# myCar.net
KiCad netlist of a schematic drawn in Altium Designer
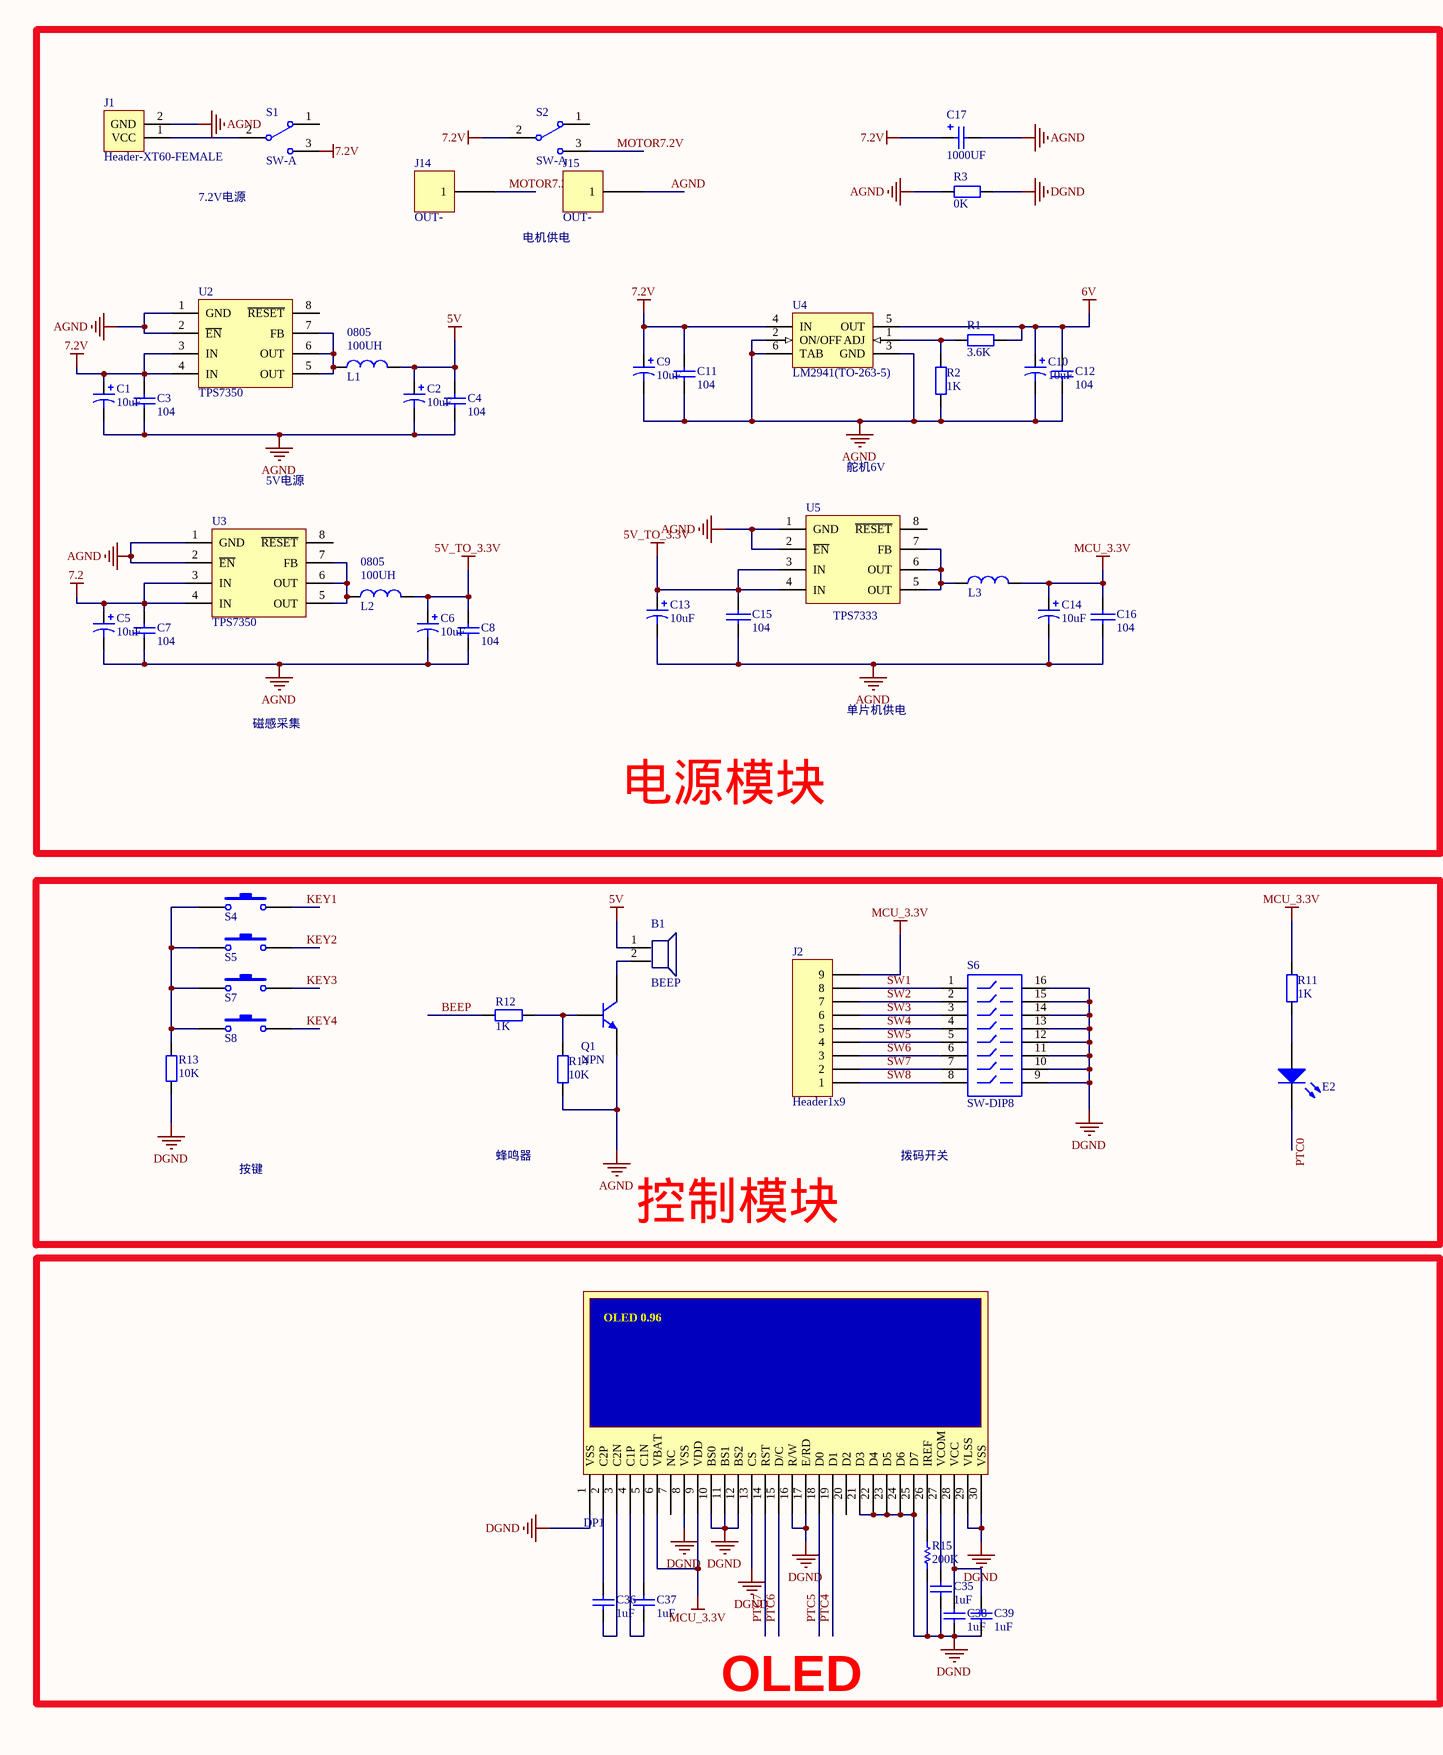
[diagram p0: myCar.SchDoc, left]
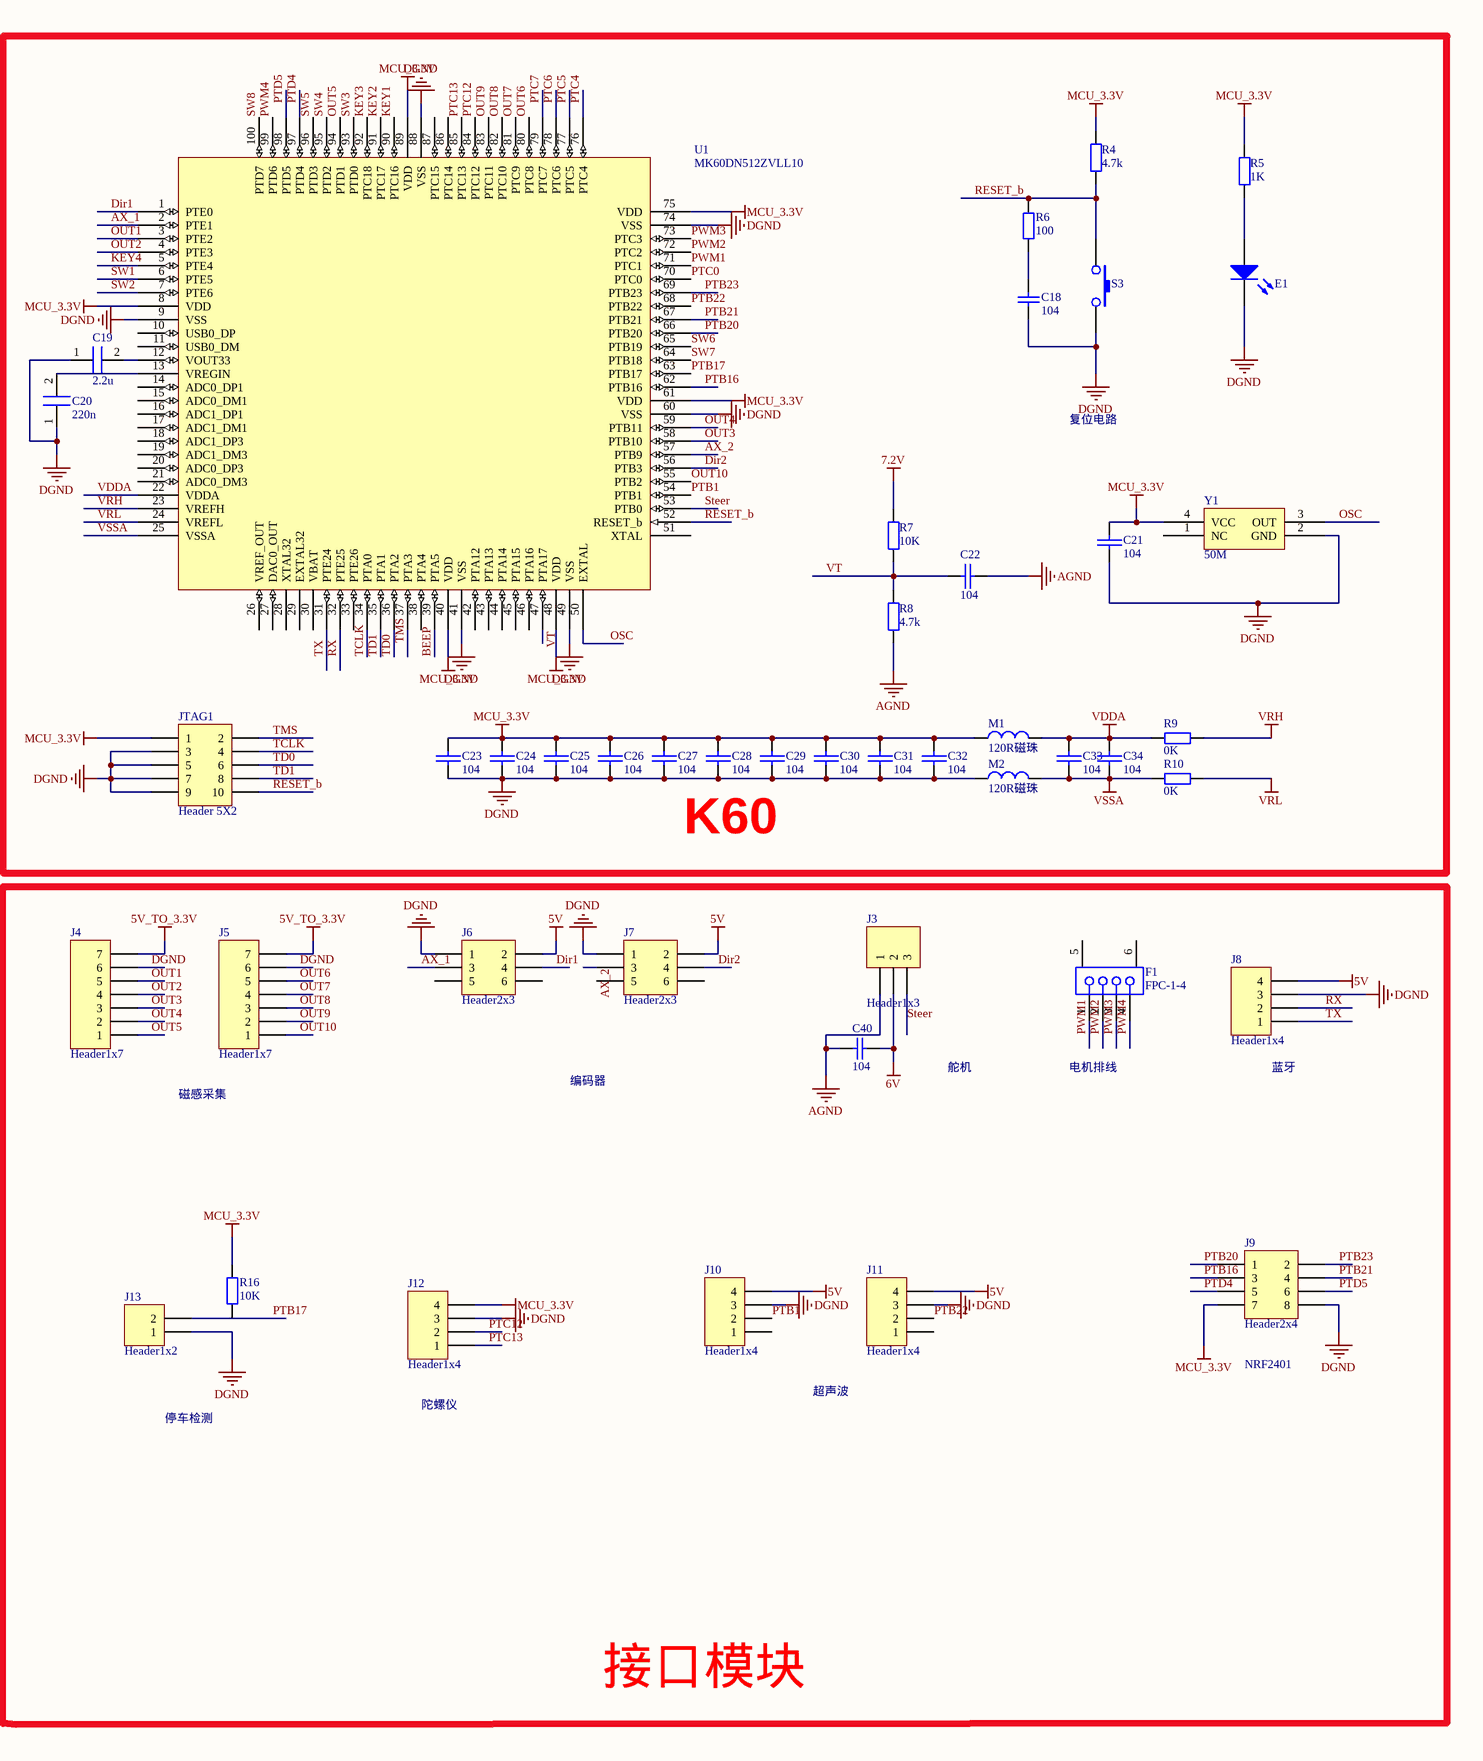
[diagram p1: myCar.SchDoc, right]

(export (version "E")
  (design (tool "Eeschema 10.0.6"))
  (components
    (comp (ref "B1") (value "BEEP") (footprint "BEEP0905") (libsource (lib "进击的袋鼠主板") (part "BEEP0905")))
    (comp (ref "C1")
      (value "10uF")
      (footprint "CAP_3216（1206）")
      (description "Polarized Capacitor (Radial)")
      (fields (field (name "Comment") "10uF/16V") (field (name "PUBLISHER") "Altium Limited"))
      (libsource (lib "进击的袋鼠主板") (part "Cap Pol1"))
    )
    (comp (ref "C2")
      (value "10uF")
      (footprint "CAP_3216（1206）")
      (description "Polarized Capacitor (Radial)")
      (fields (field (name "Comment") "10uF/16V") (field (name "PUBLISHER") "Altium Limited"))
      (libsource (lib "进击的袋鼠主板") (part "Cap Pol1"))
    )
    (comp (ref "C3")
      (value "104")
      (footprint "0603RC")
      (description "Capacitor")
      (fields (field (name "PUBLISHER") "Altium Limited"))
      (libsource (lib "进击的袋鼠主板") (part "Cap"))
    )
    (comp (ref "C4")
      (value "104")
      (footprint "0603RC")
      (description "Capacitor")
      (fields (field (name "PUBLISHER") "Altium Limited"))
      (libsource (lib "进击的袋鼠主板") (part "Cap"))
    )
    (comp (ref "C5")
      (value "10uF")
      (footprint "CAP_3216（1206）")
      (description "Polarized Capacitor (Radial)")
      (fields (field (name "Comment") "10uF/16V") (field (name "PUBLISHER") "Altium Limited"))
      (libsource (lib "进击的袋鼠主板") (part "Cap Pol1"))
    )
    (comp (ref "C6")
      (value "10uF")
      (footprint "CAP_3216（1206）")
      (description "Polarized Capacitor (Radial)")
      (fields (field (name "Comment") "10uF/16V") (field (name "PUBLISHER") "Altium Limited"))
      (libsource (lib "进击的袋鼠主板") (part "Cap Pol1"))
    )
    (comp (ref "C7")
      (value "104")
      (footprint "0603RC")
      (description "Capacitor")
      (fields (field (name "PUBLISHER") "Altium Limited"))
      (libsource (lib "进击的袋鼠主板") (part "Cap"))
    )
    (comp (ref "C8")
      (value "104")
      (footprint "0603RC")
      (description "Capacitor")
      (fields (field (name "PUBLISHER") "Altium Limited"))
      (libsource (lib "进击的袋鼠主板") (part "Cap"))
    )
    (comp (ref "C9")
      (value "10uF")
      (footprint "CAP_3216（1206）")
      (description "Polarized Capacitor (Radial)")
      (fields (field (name "Comment") "10uF/16V") (field (name "PUBLISHER") "Altium Limited"))
      (libsource (lib "进击的袋鼠主板") (part "Cap Pol1"))
    )
    (comp (ref "C10")
      (value "10uF")
      (footprint "CAP_3216（1206）")
      (description "Polarized Capacitor (Radial)")
      (fields (field (name "Comment") "10uF/16V") (field (name "PUBLISHER") "Altium Limited"))
      (libsource (lib "进击的袋鼠主板") (part "Cap Pol1"))
    )
    (comp (ref "C11")
      (value "104")
      (footprint "0603RC")
      (description "Capacitor")
      (fields (field (name "PUBLISHER") "Altium Limited"))
      (libsource (lib "进击的袋鼠主板") (part "Cap"))
    )
    (comp (ref "C12")
      (value "104")
      (footprint "0603RC")
      (description "Capacitor")
      (fields (field (name "PUBLISHER") "Altium Limited"))
      (libsource (lib "进击的袋鼠主板") (part "Cap"))
    )
    (comp (ref "C13")
      (value "10uF")
      (footprint "CAP_3216（1206）")
      (description "Polarized Capacitor (Radial)")
      (fields (field (name "Comment") "10uF/16V") (field (name "PUBLISHER") "Altium Limited"))
      (libsource (lib "进击的袋鼠主板") (part "Cap Pol1"))
    )
    (comp (ref "C14")
      (value "10uF")
      (footprint "CAP_3216（1206）")
      (description "Polarized Capacitor (Radial)")
      (fields (field (name "Comment") "10uF/16V") (field (name "PUBLISHER") "Altium Limited"))
      (libsource (lib "进击的袋鼠主板") (part "Cap Pol1"))
    )
    (comp (ref "C15")
      (value "104")
      (footprint "0603RC")
      (description "Capacitor")
      (libsource (lib "进击的袋鼠主板") (part "CAP_1"))
    )
    (comp (ref "C16")
      (value "104")
      (footprint "0603RC")
      (description "Capacitor")
      (libsource (lib "进击的袋鼠主板") (part "CAP_1"))
    )
    (comp (ref "C17")
      (value "CAP-SMD-1000UF")
      (footprint "CAP-SMD-1000UF")
      (fields (field (name "ALTIUM_UNNAMED_1") "1000UF"))
      (libsource (lib "进击的袋鼠主板") (part "CAP-SMD-1000UF"))
    )
    (comp (ref "C18")
      (value "104")
      (footprint "0603RC")
      (description "Capacitor")
      (fields (field (name "PUBLISHER") "Altium Limited"))
      (libsource (lib "进击的袋鼠主板") (part "Cap"))
    )
    (comp (ref "C19")
      (value "C0603")
      (footprint "0603RC")
      (fields (field (name "C") "2.2u"))
      (libsource (lib "进击的袋鼠主板") (part "C0603"))
    )
    (comp (ref "C20")
      (value "C0603")
      (footprint "0603RC")
      (fields (field (name "C") "220n"))
      (libsource (lib "进击的袋鼠主板") (part "C0603"))
    )
    (comp (ref "C21")
      (value "104")
      (footprint "0603RC")
      (description "Capacitor")
      (libsource (lib "进击的袋鼠主板") (part "CAP_1"))
    )
    (comp (ref "C22")
      (value "104")
      (footprint "0603RC")
      (description "Capacitor")
      (libsource (lib "进击的袋鼠主板") (part "CAP_1"))
    )
    (comp (ref "C23")
      (value "104")
      (footprint "0603RC")
      (description "Capacitor")
      (libsource (lib "进击的袋鼠主板") (part "CAP_1"))
    )
    (comp (ref "C24")
      (value "104")
      (footprint "0603RC")
      (description "Capacitor")
      (libsource (lib "进击的袋鼠主板") (part "CAP_1"))
    )
    (comp (ref "C25")
      (value "104")
      (footprint "0603RC")
      (description "Capacitor")
      (libsource (lib "进击的袋鼠主板") (part "CAP_1"))
    )
    (comp (ref "C26")
      (value "104")
      (footprint "0603RC")
      (description "Capacitor")
      (libsource (lib "进击的袋鼠主板") (part "CAP_1"))
    )
    (comp (ref "C27")
      (value "104")
      (footprint "0603RC")
      (description "Capacitor")
      (libsource (lib "进击的袋鼠主板") (part "CAP_1"))
    )
    (comp (ref "C28")
      (value "104")
      (footprint "0603RC")
      (description "Capacitor")
      (libsource (lib "进击的袋鼠主板") (part "CAP_1"))
    )
    (comp (ref "C29")
      (value "104")
      (footprint "0603RC")
      (description "Capacitor")
      (libsource (lib "进击的袋鼠主板") (part "CAP_1"))
    )
    (comp (ref "C30")
      (value "104")
      (footprint "0603RC")
      (description "Capacitor")
      (libsource (lib "进击的袋鼠主板") (part "CAP_1"))
    )
    (comp (ref "C31")
      (value "104")
      (footprint "0603RC")
      (description "Capacitor")
      (libsource (lib "进击的袋鼠主板") (part "CAP_1"))
    )
    (comp (ref "C32")
      (value "104")
      (footprint "0603RC")
      (description "Capacitor")
      (libsource (lib "进击的袋鼠主板") (part "CAP_1"))
    )
    (comp (ref "C33")
      (value "104")
      (footprint "0603RC")
      (description "Capacitor")
      (libsource (lib "进击的袋鼠主板") (part "CAP_1"))
    )
    (comp (ref "C34")
      (value "104")
      (footprint "0603RC")
      (description "Capacitor")
      (libsource (lib "进击的袋鼠主板") (part "CAP_1"))
    )
    (comp (ref "C35")
      (value "1uF")
      (footprint "0603RC")
      (description "Capacitor")
      (fields (field (name "Comment") "Cap") (field (name "PUBLISHER") "Altium Limited"))
      (libsource (lib "进击的袋鼠主板") (part "Cap_2"))
    )
    (comp (ref "C36")
      (value "1uF")
      (footprint "0603RC")
      (description "Capacitor")
      (fields (field (name "Comment") "Cap") (field (name "PUBLISHER") "Altium Limited"))
      (libsource (lib "进击的袋鼠主板") (part "Cap_2"))
    )
    (comp (ref "C37")
      (value "1uF")
      (footprint "0603RC")
      (description "Capacitor")
      (fields (field (name "Comment") "Cap") (field (name "PUBLISHER") "Altium Limited"))
      (libsource (lib "进击的袋鼠主板") (part "Cap_2"))
    )
    (comp (ref "C38")
      (value "1uF")
      (footprint "0603RC")
      (description "Capacitor")
      (fields (field (name "Comment") "Cap") (field (name "PUBLISHER") "Altium Limited"))
      (libsource (lib "进击的袋鼠主板") (part "Cap_2"))
    )
    (comp (ref "C39")
      (value "1uF")
      (footprint "0603RC")
      (description "Capacitor")
      (fields (field (name "Comment") "Cap") (field (name "PUBLISHER") "Altium Limited"))
      (libsource (lib "进击的袋鼠主板") (part "Cap_2"))
    )
    (comp (ref "C40")
      (value "104")
      (footprint "0603RC")
      (description "Capacitor")
      (fields (field (name "PUBLISHER") "Altium Limited"))
      (libsource (lib "进击的袋鼠主板") (part "Cap"))
    )
    (comp (ref "DP1") (value "OLED") (footprint "OLED_0.96") (libsource (lib "进击的袋鼠主板") (part "OLED-0.96")))
    (comp (ref "E1")
      (value "LED0")
      (footprint "LED-0603")
      (description "Typical INFRARED GaAs LED")
      (fields (field (name "PUBLISHER") "Altium Limited"))
      (libsource (lib "进击的袋鼠主板") (part "LED0"))
    )
    (comp (ref "E2")
      (value "LED0")
      (footprint "LED-0603")
      (description "Typical INFRARED GaAs LED")
      (fields (field (name "PUBLISHER") "Altium Limited"))
      (libsource (lib "进击的袋鼠主板") (part "LED0"))
    )
    (comp (ref "F1") (value "FPC-1-4") (footprint "FPC-1-4") (libsource (lib "进击的袋鼠主板") (part "FPC-1-4")))
    (comp (ref "J1")
      (value "Header-XT60-FEMALE")
      (footprint "HEADER-XT60-FEMALE")
      (description "航模接头")
      (libsource (lib "进击的袋鼠主板") (part "Header-XT60-FEMALE"))
    )
    (comp (ref "J2")
      (value "Header1x9")
      (footprint "HEADER1X9")
      (libsource (lib "Connector_zlh") (part "Header1x9"))
    )
    (comp (ref "J3")
      (value "Header1x3")
      (footprint "HEADER1X3")
      (libsource (lib "进击的袋鼠主板") (part "Header1x3"))
    )
    (comp (ref "J4")
      (value "Header1x7")
      (footprint "HEADER1X7")
      (libsource (lib "lw_connector") (part "Header1x7"))
    )
    (comp (ref "J5")
      (value "Header1x7")
      (footprint "HEADER1X7")
      (libsource (lib "lw_connector") (part "Header1x7"))
    )
    (comp (ref "J6")
      (value "Header2x3")
      (footprint "HEADER2X3")
      (libsource (lib "进击的袋鼠主板") (part "Header2x3"))
    )
    (comp (ref "J7")
      (value "Header2x3")
      (footprint "HEADER2X3")
      (libsource (lib "进击的袋鼠主板") (part "Header2x3"))
    )
    (comp (ref "J8")
      (value "Header1x4")
      (footprint "HEADER1X4")
      (libsource (lib "进击的袋鼠主板") (part "Header1x4"))
    )
    (comp (ref "J9")
      (value "Header2x4")
      (footprint "HEADER2X4")
      (libsource (lib "进击的袋鼠主板") (part "Header2x4"))
    )
    (comp (ref "J10")
      (value "Header1x4")
      (footprint "HEADER1X4")
      (libsource (lib "进击的袋鼠主板") (part "Header1x4"))
    )
    (comp (ref "J11")
      (value "Header1x4")
      (footprint "HEADER1X4")
      (libsource (lib "进击的袋鼠主板") (part "Header1x4"))
    )
    (comp (ref "J12")
      (value "Header1x4")
      (footprint "HEADER1X4")
      (libsource (lib "进击的袋鼠主板") (part "Header1x4"))
    )
    (comp (ref "J13")
      (value "Header1x2")
      (footprint "HEADER1X2")
      (libsource (lib "进击的袋鼠主板") (part "Header1x2"))
    )
    (comp (ref "J14") (value "OUT-") (footprint "HEADER1X1") (libsource (lib "qudong") (part "Header1x1")))
    (comp (ref "J15") (value "OUT-") (footprint "HEADER1X1") (libsource (lib "qudong") (part "Header1x1")))
    (comp (ref "JTAG1")
      (value "Header 5X2")
      (footprint "HEADER2X5")
      (description "Header, 5-Pin, Dual row")
      (fields (field (name "PUBLISHER") "Altium Limited"))
      (libsource (lib "进击的袋鼠主板") (part "Header 5X2"))
    )
    (comp (ref "L1")
      (value "INTUCTOR")
      (footprint "L0805 - duplicate")
      (libsource (lib "进击的袋鼠主板") (part "INTUCTOR"))
    )
    (comp (ref "L2")
      (value "INTUCTOR")
      (footprint "L0805 - duplicate")
      (libsource (lib "进击的袋鼠主板") (part "INTUCTOR"))
    )
    (comp (ref "L3")
      (value "INTUCTOR")
      (footprint "L0805 - duplicate")
      (libsource (lib "进击的袋鼠主板") (part "INTUCTOR"))
    )
    (comp (ref "M1") (value "120R磁珠") (footprint "bead0805") (libsource (lib "进击的袋鼠主板") (part "磁珠")))
    (comp (ref "M2") (value "120R磁珠") (footprint "bead0805") (libsource (lib "进击的袋鼠主板") (part "磁珠")))
    (comp (ref "Q1")
      (value "NPN")
      (footprint "SOT-23")
      (description "NPN Bipolar Transistor")
      (fields (field (name "PUBLISHER") "Altium Limited"))
      (libsource (lib "进击的袋鼠主板") (part "NPN(SOT-23)"))
    )
    (comp (ref "R1")
      (value "RES")
      (footprint "0603RC")
      (fields (field (name "ALTIUM_UNNAMED_1") "3.6K"))
      (libsource (lib "进击的袋鼠主板") (part "RES"))
    )
    (comp (ref "R2")
      (value "1K")
      (footprint "0603RC")
      (description "Resistor")
      (fields (field (name "PUBLISHER") "Altium Limited"))
      (libsource (lib "") (part "Res2_1"))
    )
    (comp (ref "R3")
      (value "RES")
      (footprint "0603RC")
      (fields (field (name "ALTIUM_UNNAMED_1") "0K"))
      (libsource (lib "进击的袋鼠主板") (part "RES"))
    )
    (comp (ref "R4")
      (value "4.7k")
      (footprint "0603RC")
      (description "Resistor")
      (fields (field (name "Comment") "2K") (field (name "PUBLISHER") "Altium Limited"))
      (libsource (lib "进击的袋鼠主板") (part "Res2_2"))
    )
    (comp (ref "R5")
      (value "1K")
      (footprint "0603RC")
      (description "Resistor")
      (fields (field (name "PUBLISHER") "Altium Limited"))
      (libsource (lib "") (part "Res2_1"))
    )
    (comp (ref "R6")
      (value "RES")
      (footprint "0603RC")
      (fields (field (name "ALTIUM_UNNAMED_1") "100"))
      (libsource (lib "进击的袋鼠主板") (part "RES"))
    )
    (comp (ref "R7")
      (value "10K")
      (footprint "0603RC")
      (description "Resistor")
      (fields (field (name "PUBLISHER") "Altium Limited"))
      (libsource (lib "进击的袋鼠主板") (part "Res2_1"))
    )
    (comp (ref "R8")
      (value "4.7k")
      (footprint "0603RC")
      (description "Resistor")
      (fields (field (name "Comment") "2K") (field (name "PUBLISHER") "Altium Limited"))
      (libsource (lib "进击的袋鼠主板") (part "Res2_2"))
    )
    (comp (ref "R9")
      (value "RES")
      (footprint "0603RC")
      (fields (field (name "ALTIUM_UNNAMED_1") "0K"))
      (libsource (lib "进击的袋鼠主板") (part "RES"))
    )
    (comp (ref "R10")
      (value "RES")
      (footprint "0603RC")
      (fields (field (name "ALTIUM_UNNAMED_1") "0K"))
      (libsource (lib "进击的袋鼠主板") (part "RES"))
    )
    (comp (ref "R11")
      (value "1K")
      (footprint "0603RC")
      (description "Resistor")
      (fields (field (name "PUBLISHER") "Altium Limited"))
      (libsource (lib "") (part "Res2_1"))
    )
    (comp (ref "R12")
      (value "1K")
      (footprint "0603RC")
      (description "Resistor")
      (fields (field (name "PUBLISHER") "Altium Limited"))
      (libsource (lib "进击的袋鼠主板") (part "Res2"))
    )
    (comp (ref "R13")
      (value "RES")
      (footprint "0603RC")
      (fields (field (name "ALTIUM_UNNAMED_1") "10K"))
      (libsource (lib "进击的袋鼠主板") (part "RES"))
    )
    (comp (ref "R14")
      (value "10K")
      (footprint "0603RC")
      (description "Resistor")
      (fields (field (name "PUBLISHER") "Altium Limited"))
      (libsource (lib "进击的袋鼠主板") (part "Res2_1"))
    )
    (comp (ref "R15")
      (value "200K")
      (footprint "0603RC")
      (description "贴片电阻")
      (fields (field (name "Comment") "Res") (field (name "PUBLISHER") "Altium Limited"))
      (libsource (lib "进击的袋鼠主板") (part "Res_1"))
    )
    (comp (ref "R16")
      (value "RES")
      (footprint "0603RC")
      (fields (field (name "ALTIUM_UNNAMED_1") "10K"))
      (libsource (lib "进击的袋鼠主板") (part "RES"))
    )
    (comp (ref "S1") (value "SW-A") (footprint "SW-B") (libsource (lib "进击的袋鼠主板") (part "SW-A")))
    (comp (ref "S2") (value "SW-A") (footprint "SW-B") (libsource (lib "进击的袋鼠主板") (part "SW-A")))
    (comp (ref "S3") (value "SW-PB") (footprint "SWITCH") (libsource (lib "进击的袋鼠主板") (part "SW-PB_SMT")))
    (comp (ref "S4")
      (value "SW-PB")
      (footprint "SWITCH")
      (description "Switch")
      (fields (field (name "PUBLISHER") "Altium Limited"))
      (libsource (lib "进击的袋鼠主板") (part "SW-PB"))
    )
    (comp (ref "S5")
      (value "SW-PB")
      (footprint "SWITCH")
      (description "Switch")
      (fields (field (name "PUBLISHER") "Altium Limited"))
      (libsource (lib "进击的袋鼠主板") (part "SW-PB"))
    )
    (comp (ref "S6") (value "SW-DIP8") (footprint "DIP-16") (libsource (lib "lw_common") (part "SW-DIP8")))
    (comp (ref "S7")
      (value "SW-PB")
      (footprint "SWITCH")
      (description "Switch")
      (fields (field (name "PUBLISHER") "Altium Limited"))
      (libsource (lib "进击的袋鼠主板") (part "SW-PB"))
    )
    (comp (ref "S8")
      (value "SW-PB")
      (footprint "SWITCH")
      (description "Switch")
      (fields (field (name "PUBLISHER") "Altium Limited"))
      (libsource (lib "进击的袋鼠主板") (part "SW-PB"))
    )
    (comp (ref "U1")
      (value "MK60DN512ZVLL10")
      (footprint "QFP100")
      (libsource (lib "进击的袋鼠主板") (part "MK60DN512ZVLL10"))
    )
    (comp (ref "U2")
      (value "TPS7350")
      (footprint "TPS7350(7333)")
      (libsource (lib "进击的袋鼠主板") (part "TPS7350"))
    )
    (comp (ref "U3")
      (value "TPS7350")
      (footprint "TPS7350(7333)")
      (libsource (lib "进击的袋鼠主板") (part "TPS7350"))
    )
    (comp (ref "U4")
      (value "LM2941(TO-263-5)")
      (footprint "TO-263-5")
      (libsource (lib "进击的袋鼠主板") (part "LM2941(TO-263-5)"))
    )
    (comp (ref "U5")
      (value "TPS7333")
      (footprint "TPS7350(7333)")
      (libsource (lib "进击的袋鼠主板") (part "TPS7350"))
    )
    (comp (ref "Y1") (value "50M") (footprint "50M晶振(5032)") (libsource (lib "进击的袋鼠主板") (part "XTAL_S")))
  )
  (nets
    (net (code "1") (name "/AX_1") (class "Default")
      (node (ref "J6") (pin "3") (pinfunction "3_3") (pintype "passive"))
      (node (ref "U1") (pin "2") (pinfunction "PTE1_2") (pintype "bidirectional"))
    )
    (net (code "2") (name "/AX_2") (class "Default")
      (node (ref "J7") (pin "3") (pinfunction "3_3") (pintype "passive"))
      (node (ref "U1") (pin "57") (pinfunction "PTB9_57") (pintype "bidirectional"))
    )
    (net (code "3") (name "/BEEP") (class "Default")
      (node (ref "R12") (pin "1") (pinfunction "1_1") (pintype "passive"))
      (node (ref "U1") (pin "39") (pinfunction "PTA5_39") (pintype "bidirectional"))
    )
    (net (code "4") (name "/Dir1") (class "Default")
      (node (ref "J6") (pin "4") (pinfunction "4_4") (pintype "passive"))
      (node (ref "U1") (pin "1") (pinfunction "PTE0_1") (pintype "bidirectional"))
    )
    (net (code "5") (name "/Dir2") (class "Default")
      (node (ref "J7") (pin "4") (pinfunction "4_4") (pintype "passive"))
      (node (ref "U1") (pin "56") (pinfunction "PTB3_56") (pintype "bidirectional"))
    )
    (net (code "6") (name "/KEY1") (class "Default")
      (node (ref "S4") (pin "2") (pinfunction "2_2") (pintype "passive"))
      (node (ref "U1") (pin "90") (pinfunction "PTC16_90") (pintype "bidirectional"))
    )
    (net (code "7") (name "/KEY2") (class "Default")
      (node (ref "S5") (pin "2") (pinfunction "2_2") (pintype "passive"))
      (node (ref "U1") (pin "91") (pinfunction "PTC17_91") (pintype "bidirectional"))
    )
    (net (code "8") (name "/KEY3") (class "Default")
      (node (ref "S7") (pin "2") (pinfunction "2_2") (pintype "passive"))
      (node (ref "U1") (pin "92") (pinfunction "PTC18_92") (pintype "bidirectional"))
    )
    (net (code "9") (name "/KEY4") (class "Default")
      (node (ref "S8") (pin "2") (pinfunction "2_2") (pintype "passive"))
      (node (ref "U1") (pin "5") (pinfunction "PTE4_5") (pintype "bidirectional"))
    )
    (net (code "10") (name "/MOTOR7.2V") (class "Default")
      (node (ref "J14") (pin "1") (pinfunction "1_1") (pintype "passive"))
      (node (ref "S2") (pin "3") (pinfunction "3_3") (pintype "passive"))
    )
    (net (code "11") (name "/OSC") (class "Default")
      (node (ref "U1") (pin "50") (pinfunction "EXTAL_50") (pintype "passive"))
      (node (ref "Y1") (pin "3") (pinfunction "OUT_3") (pintype "passive"))
    )
    (net (code "12") (name "/OUT1") (class "Default")
      (node (ref "J4") (pin "5") (pinfunction "5_5") (pintype "passive"))
      (node (ref "U1") (pin "3") (pinfunction "PTE2_3") (pintype "bidirectional"))
    )
    (net (code "13") (name "/OUT2") (class "Default")
      (node (ref "J4") (pin "4") (pinfunction "4_4") (pintype "passive"))
      (node (ref "U1") (pin "4") (pinfunction "PTE3_4") (pintype "bidirectional"))
    )
    (net (code "14") (name "/OUT3") (class "Default")
      (node (ref "J4") (pin "3") (pinfunction "3_3") (pintype "passive"))
      (node (ref "U1") (pin "58") (pinfunction "PTB10_58") (pintype "bidirectional"))
    )
    (net (code "15") (name "/OUT4") (class "Default")
      (node (ref "J4") (pin "2") (pinfunction "2_2") (pintype "passive"))
      (node (ref "U1") (pin "59") (pinfunction "PTB11_59") (pintype "bidirectional"))
    )
    (net (code "16") (name "/OUT5") (class "Default")
      (node (ref "J4") (pin "1") (pinfunction "1_1") (pintype "passive"))
      (node (ref "U1") (pin "94") (pinfunction "PTD1_94") (pintype "bidirectional"))
    )
    (net (code "17") (name "/OUT6") (class "Default")
      (node (ref "J5") (pin "5") (pinfunction "5_5") (pintype "passive"))
      (node (ref "U1") (pin "80") (pinfunction "PTC8_80") (pintype "bidirectional"))
    )
    (net (code "18") (name "/OUT7") (class "Default")
      (node (ref "J5") (pin "4") (pinfunction "4_4") (pintype "passive"))
      (node (ref "U1") (pin "81") (pinfunction "PTC9_81") (pintype "bidirectional"))
    )
    (net (code "19") (name "/OUT8") (class "Default")
      (node (ref "J5") (pin "3") (pinfunction "3_3") (pintype "passive"))
      (node (ref "U1") (pin "82") (pinfunction "PTC10_82") (pintype "bidirectional"))
    )
    (net (code "20") (name "/OUT9") (class "Default")
      (node (ref "J5") (pin "2") (pinfunction "2_2") (pintype "passive"))
      (node (ref "U1") (pin "83") (pinfunction "PTC11_83") (pintype "bidirectional"))
    )
    (net (code "21") (name "/OUT10") (class "Default")
      (node (ref "J5") (pin "1") (pinfunction "1_1") (pintype "passive"))
      (node (ref "U1") (pin "55") (pinfunction "PTB2_55") (pintype "bidirectional"))
    )
    (net (code "22") (name "/PTB1") (class "Default")
      (node (ref "J10") (pin "2") (pinfunction "2_2") (pintype "passive"))
      (node (ref "U1") (pin "54") (pinfunction "PTB1_54") (pintype "bidirectional"))
    )
    (net (code "23") (name "/PTB16") (class "Default")
      (node (ref "J9") (pin "3") (pinfunction "3_3") (pintype "passive"))
      (node (ref "U1") (pin "62") (pinfunction "PTB16_62") (pintype "bidirectional"))
    )
    (net (code "24") (name "/PTB17") (class "Default")
      (node (ref "J13") (pin "2") (pinfunction "2_2") (pintype "passive"))
      (node (ref "U1") (pin "63") (pinfunction "PTB17_63") (pintype "bidirectional"))
    )
    (net (code "25") (name "/PTB20") (class "Default")
      (node (ref "J9") (pin "1") (pinfunction "1_1") (pintype "passive"))
      (node (ref "U1") (pin "66") (pinfunction "PTB20_66") (pintype "bidirectional"))
    )
    (net (code "26") (name "/PTB21") (class "Default")
      (node (ref "J9") (pin "4") (pinfunction "4_4") (pintype "passive"))
      (node (ref "U1") (pin "67") (pinfunction "PTB21_67") (pintype "bidirectional"))
    )
    (net (code "27") (name "/PTB22") (class "Default")
      (node (ref "J11") (pin "2") (pinfunction "2_2") (pintype "passive"))
      (node (ref "U1") (pin "68") (pinfunction "PTB22_68") (pintype "bidirectional"))
    )
    (net (code "28") (name "/PTB23") (class "Default")
      (node (ref "J9") (pin "2") (pinfunction "2_2") (pintype "passive"))
      (node (ref "U1") (pin "69") (pinfunction "PTB23_69") (pintype "bidirectional"))
    )
    (net (code "29") (name "/PTC0") (class "Default")
      (node (ref "E2") (pin "2") (pinfunction "2_2") (pintype "passive"))
      (node (ref "U1") (pin "70") (pinfunction "PTC0_70") (pintype "bidirectional"))
    )
    (net (code "30") (name "/PTC4") (class "Default")
      (node (ref "DP1") (pin "19") (pinfunction "D1_19") (pintype "passive"))
      (node (ref "U1") (pin "76") (pinfunction "PTC4_76") (pintype "bidirectional"))
    )
    (net (code "31") (name "/PTC5") (class "Default")
      (node (ref "DP1") (pin "18") (pinfunction "D0_18") (pintype "passive"))
      (node (ref "U1") (pin "77") (pinfunction "PTC5_77") (pintype "bidirectional"))
    )
    (net (code "32") (name "/PTC6") (class "Default")
      (node (ref "DP1") (pin "15") (pinfunction "D/C_15") (pintype "passive"))
      (node (ref "U1") (pin "78") (pinfunction "PTC6_78") (pintype "bidirectional"))
    )
    (net (code "33") (name "/PTC7") (class "Default")
      (node (ref "DP1") (pin "14") (pinfunction "RST_14") (pintype "passive"))
      (node (ref "U1") (pin "79") (pinfunction "PTC7_79") (pintype "bidirectional"))
    )
    (net (code "34") (name "/PTC12") (class "Default")
      (node (ref "J12") (pin "2") (pinfunction "2_2") (pintype "passive"))
      (node (ref "U1") (pin "84") (pinfunction "PTC12_84") (pintype "bidirectional"))
    )
    (net (code "35") (name "/PTC13") (class "Default")
      (node (ref "J12") (pin "1") (pinfunction "1_1") (pintype "passive"))
      (node (ref "U1") (pin "85") (pinfunction "PTC13_85") (pintype "bidirectional"))
    )
    (net (code "36") (name "/PTD4") (class "Default")
      (node (ref "J9") (pin "5") (pinfunction "5_5") (pintype "passive"))
      (node (ref "U1") (pin "97") (pinfunction "PTD4_97") (pintype "bidirectional"))
    )
    (net (code "37") (name "/PTD5") (class "Default")
      (node (ref "J9") (pin "6") (pinfunction "6_6") (pintype "passive"))
      (node (ref "U1") (pin "98") (pinfunction "PTD5_98") (pintype "bidirectional"))
    )
    (net (code "38") (name "/PWM1") (class "Default")
      (node (ref "F1") (pin "1") (pinfunction "1_1") (pintype "passive"))
      (node (ref "U1") (pin "71") (pinfunction "PTC1_71") (pintype "bidirectional"))
    )
    (net (code "39") (name "/PWM2") (class "Default")
      (node (ref "F1") (pin "2") (pinfunction "2_2") (pintype "passive"))
      (node (ref "U1") (pin "72") (pinfunction "PTC2_72") (pintype "bidirectional"))
    )
    (net (code "40") (name "/PWM3") (class "Default")
      (node (ref "F1") (pin "3") (pinfunction "3_3") (pintype "passive"))
      (node (ref "U1") (pin "73") (pinfunction "PTC3_73") (pintype "bidirectional"))
    )
    (net (code "41") (name "/PWM4") (class "Default")
      (node (ref "F1") (pin "4") (pinfunction "4_4") (pintype "passive"))
      (node (ref "U1") (pin "99") (pinfunction "PTD6_99") (pintype "bidirectional"))
    )
    (net (code "42") (name "/RESET_b") (class "Default")
      (node (ref "JTAG1") (pin "10") (pinfunction "10_10") (pintype "passive"))
      (node (ref "R4") (pin "1") (pinfunction "1_1") (pintype "passive"))
      (node (ref "R6") (pin "2") (pinfunction "2_2") (pintype "passive"))
      (node (ref "S3") (pin "1") (pinfunction "1_1") (pintype "passive"))
      (node (ref "U1") (pin "52") (pinfunction "RESET_b_52") (pintype "input"))
    )
    (net (code "43") (name "/RX") (class "Default")
      (node (ref "J8") (pin "2") (pinfunction "2_2") (pintype "passive"))
      (node (ref "U1") (pin "32") (pinfunction "PTE25_32") (pintype "bidirectional"))
    )
    (net (code "44") (name "/SW1") (class "Default")
      (node (ref "J2") (pin "8") (pinfunction "8_8") (pintype "passive"))
      (node (ref "S6") (pin "1") (pinfunction "1_1") (pintype "passive"))
      (node (ref "U1") (pin "6") (pinfunction "PTE5_6") (pintype "bidirectional"))
    )
    (net (code "45") (name "/SW2") (class "Default")
      (node (ref "J2") (pin "7") (pinfunction "7_7") (pintype "passive"))
      (node (ref "S6") (pin "2") (pinfunction "2_2") (pintype "passive"))
      (node (ref "U1") (pin "7") (pinfunction "PTE6_7") (pintype "bidirectional"))
    )
    (net (code "46") (name "/SW3") (class "Default")
      (node (ref "J2") (pin "6") (pinfunction "6_6") (pintype "passive"))
      (node (ref "S6") (pin "3") (pinfunction "3_3") (pintype "passive"))
      (node (ref "U1") (pin "93") (pinfunction "PTD0_93") (pintype "bidirectional"))
    )
    (net (code "47") (name "/SW4") (class "Default")
      (node (ref "J2") (pin "5") (pinfunction "5_5") (pintype "passive"))
      (node (ref "S6") (pin "4") (pinfunction "4_4") (pintype "passive"))
      (node (ref "U1") (pin "95") (pinfunction "PTD2_95") (pintype "bidirectional"))
    )
    (net (code "48") (name "/SW5") (class "Default")
      (node (ref "J2") (pin "4") (pinfunction "4_4") (pintype "passive"))
      (node (ref "S6") (pin "5") (pinfunction "5_5") (pintype "passive"))
      (node (ref "U1") (pin "96") (pinfunction "PTD3_96") (pintype "bidirectional"))
    )
    (net (code "49") (name "/SW6") (class "Default")
      (node (ref "J2") (pin "3") (pinfunction "3_3") (pintype "passive"))
      (node (ref "S6") (pin "6") (pinfunction "6_6") (pintype "passive"))
      (node (ref "U1") (pin "65") (pinfunction "PTB19_65") (pintype "bidirectional"))
    )
    (net (code "50") (name "/SW7") (class "Default")
      (node (ref "J2") (pin "2") (pinfunction "2_2") (pintype "passive"))
      (node (ref "S6") (pin "7") (pinfunction "7_7") (pintype "passive"))
      (node (ref "U1") (pin "64") (pinfunction "PTB18_64") (pintype "bidirectional"))
    )
    (net (code "51") (name "/SW8") (class "Default")
      (node (ref "J2") (pin "1") (pinfunction "1_1") (pintype "passive"))
      (node (ref "S6") (pin "8") (pinfunction "8_8") (pintype "passive"))
      (node (ref "U1") (pin "100") (pinfunction "PTD7_100") (pintype "bidirectional"))
    )
    (net (code "52") (name "/Steer") (class "Default")
      (node (ref "J3") (pin "3") (pinfunction "3_3") (pintype "passive"))
      (node (ref "U1") (pin "53") (pinfunction "PTB0_53") (pintype "bidirectional"))
    )
    (net (code "53") (name "/TCLK") (class "Default")
      (node (ref "JTAG1") (pin "4") (pinfunction "4_4") (pintype "passive"))
      (node (ref "U1") (pin "34") (pinfunction "PTA0_34") (pintype "bidirectional"))
    )
    (net (code "54") (name "/TD0") (class "Default")
      (node (ref "JTAG1") (pin "6") (pinfunction "6_6") (pintype "passive"))
      (node (ref "U1") (pin "36") (pinfunction "PTA2_36") (pintype "bidirectional"))
    )
    (net (code "55") (name "/TD1") (class "Default")
      (node (ref "JTAG1") (pin "8") (pinfunction "8_8") (pintype "passive"))
      (node (ref "U1") (pin "35") (pinfunction "PTA1_35") (pintype "bidirectional"))
    )
    (net (code "56") (name "/TMS") (class "Default")
      (node (ref "JTAG1") (pin "2") (pinfunction "2_2") (pintype "passive"))
      (node (ref "U1") (pin "37") (pinfunction "PTA3_37") (pintype "bidirectional"))
    )
    (net (code "57") (name "/TX") (class "Default")
      (node (ref "J8") (pin "1") (pinfunction "1_1") (pintype "passive"))
      (node (ref "U1") (pin "31") (pinfunction "PTE24_31") (pintype "bidirectional"))
    )
    (net (code "58") (name "/VT") (class "Default")
      (node (ref "C22") (pin "1") (pinfunction "1_1") (pintype "passive"))
      (node (ref "R7") (pin "1") (pinfunction "1_1") (pintype "passive"))
      (node (ref "R8") (pin "2") (pinfunction "2_2") (pintype "passive"))
      (node (ref "U1") (pin "47") (pinfunction "PTA17_47") (pintype "bidirectional"))
    )
    (net (code "59") (name "5V") (class "Default")
      (node (ref "B1") (pin "1") (pinfunction "VCC_1") (pintype "passive"))
      (node (ref "C2") (pin "1") (pinfunction "1_1") (pintype "passive"))
      (node (ref "C4") (pin "2") (pinfunction "2_2") (pintype "passive"))
      (node (ref "J10") (pin "4") (pinfunction "4_4") (pintype "passive"))
      (node (ref "J11") (pin "4") (pinfunction "4_4") (pintype "passive"))
      (node (ref "J6") (pin "2") (pinfunction "2_2") (pintype "passive"))
      (node (ref "J7") (pin "2") (pinfunction "2_2") (pintype "passive"))
      (node (ref "J8") (pin "4") (pinfunction "4_4") (pintype "passive"))
      (node (ref "L1") (pin "2") (pinfunction "2_2") (pintype "passive"))
    )
    (net (code "60") (name "5V_TO_3.3V") (class "Default")
      (node (ref "C13") (pin "1") (pinfunction "1_1") (pintype "passive"))
      (node (ref "C15") (pin "1") (pinfunction "1_1") (pintype "passive"))
      (node (ref "C6") (pin "1") (pinfunction "1_1") (pintype "passive"))
      (node (ref "C8") (pin "1") (pinfunction "1_1") (pintype "passive"))
      (node (ref "J4") (pin "7") (pinfunction "7_7") (pintype "passive"))
      (node (ref "J5") (pin "7") (pinfunction "7_7") (pintype "passive"))
      (node (ref "L2") (pin "2") (pinfunction "2_2") (pintype "passive"))
      (node (ref "U5") (pin "3") (pinfunction "IN_3") (pintype "power_in"))
      (node (ref "U5") (pin "4") (pinfunction "IN_4") (pintype "power_in"))
    )
    (net (code "61") (name "6V") (class "Default")
      (node (ref "C10") (pin "1") (pinfunction "1_1") (pintype "passive"))
      (node (ref "C12") (pin "2") (pinfunction "2_2") (pintype "passive"))
      (node (ref "C40") (pin "2") (pinfunction "2_2") (pintype "passive"))
      (node (ref "J3") (pin "2") (pinfunction "2_2") (pintype "passive"))
      (node (ref "R1") (pin "2") (pinfunction "2_2") (pintype "passive"))
      (node (ref "U4") (pin "5") (pinfunction "OUT_5") (pintype "power_in"))
    )
    (net (code "62") (name "7.2") (class "Default")
      (node (ref "C5") (pin "1") (pinfunction "1_1") (pintype "passive"))
      (node (ref "C7") (pin "2") (pinfunction "2_2") (pintype "passive"))
      (node (ref "U3") (pin "3") (pinfunction "IN_3") (pintype "power_in"))
      (node (ref "U3") (pin "4") (pinfunction "IN_4") (pintype "power_in"))
    )
    (net (code "63") (name "7.2V") (class "Default")
      (node (ref "C1") (pin "1") (pinfunction "1_1") (pintype "passive"))
      (node (ref "C11") (pin "2") (pinfunction "2_2") (pintype "passive"))
      (node (ref "C17") (pin "1") (pinfunction "1_1") (pintype "passive"))
      (node (ref "C3") (pin "2") (pinfunction "2_2") (pintype "passive"))
      (node (ref "C9") (pin "1") (pinfunction "1_1") (pintype "passive"))
      (node (ref "R7") (pin "2") (pinfunction "2_2") (pintype "passive"))
      (node (ref "S1") (pin "3") (pinfunction "3_3") (pintype "passive"))
      (node (ref "S2") (pin "2") (pinfunction "2_2") (pintype "passive"))
      (node (ref "U2") (pin "3") (pinfunction "IN_3") (pintype "power_in"))
      (node (ref "U2") (pin "4") (pinfunction "IN_4") (pintype "power_in"))
      (node (ref "U4") (pin "4") (pinfunction "IN_4") (pintype "power_in"))
    )
    (net (code "64") (name "AGND") (class "Default")
      (node (ref "C1") (pin "2") (pinfunction "2_2") (pintype "passive"))
      (node (ref "C10") (pin "2") (pinfunction "2_2") (pintype "passive"))
      (node (ref "C11") (pin "1") (pinfunction "1_1") (pintype "passive"))
      (node (ref "C12") (pin "1") (pinfunction "1_1") (pintype "passive"))
      (node (ref "C13") (pin "2") (pinfunction "2_2") (pintype "passive"))
      (node (ref "C14") (pin "2") (pinfunction "2_2") (pintype "passive"))
      (node (ref "C15") (pin "2") (pinfunction "2_2") (pintype "passive"))
      (node (ref "C16") (pin "2") (pinfunction "2_2") (pintype "passive"))
      (node (ref "C17") (pin "2") (pinfunction "2_2") (pintype "passive"))
      (node (ref "C2") (pin "2") (pinfunction "2_2") (pintype "passive"))
      (node (ref "C22") (pin "2") (pinfunction "2_2") (pintype "passive"))
      (node (ref "C3") (pin "1") (pinfunction "1_1") (pintype "passive"))
      (node (ref "C4") (pin "1") (pinfunction "1_1") (pintype "passive"))
      (node (ref "C40") (pin "1") (pinfunction "1_1") (pintype "passive"))
      (node (ref "C5") (pin "2") (pinfunction "2_2") (pintype "passive"))
      (node (ref "C6") (pin "2") (pinfunction "2_2") (pintype "passive"))
      (node (ref "C7") (pin "1") (pinfunction "1_1") (pintype "passive"))
      (node (ref "C8") (pin "2") (pinfunction "2_2") (pintype "passive"))
      (node (ref "C9") (pin "2") (pinfunction "2_2") (pintype "passive"))
      (node (ref "J1") (pin "2") (pinfunction "GND_2") (pintype "passive"))
      (node (ref "J15") (pin "1") (pinfunction "1_1") (pintype "passive"))
      (node (ref "J3") (pin "1") (pinfunction "1_1") (pintype "passive"))
      (node (ref "Q1") (pin "2") (pinfunction "E_2") (pintype "passive"))
      (node (ref "R14") (pin "1") (pinfunction "1_1") (pintype "passive"))
      (node (ref "R2") (pin "1") (pinfunction "1_1") (pintype "passive"))
      (node (ref "R3") (pin "1") (pinfunction "1_1") (pintype "passive"))
      (node (ref "R8") (pin "1") (pinfunction "1_1") (pintype "passive"))
      (node (ref "U2") (pin "1") (pinfunction "GND_1") (pintype "power_in"))
      (node (ref "U2") (pin "2") (pinfunction "~{EN}_2") (pintype "power_in"))
      (node (ref "U3") (pin "1") (pinfunction "GND_1") (pintype "power_in"))
      (node (ref "U3") (pin "2") (pinfunction "~{EN}_2") (pintype "power_in"))
      (node (ref "U4") (pin "2") (pinfunction "ON/OFF_2") (pintype "input"))
      (node (ref "U4") (pin "3") (pinfunction "GND_3") (pintype "power_in"))
      (node (ref "U4") (pin "6") (pinfunction "TAB_6") (pintype "power_in"))
      (node (ref "U5") (pin "1") (pinfunction "GND_1") (pintype "power_in"))
      (node (ref "U5") (pin "2") (pinfunction "~{EN}_2") (pintype "power_in"))
    )
    (net (code "65") (name "DGND") (class "Default")
      (node (ref "C18") (pin "1") (pinfunction "1_1") (pintype "passive"))
      (node (ref "C19") (pin "1") (pintype "passive"))
      (node (ref "C20") (pin "1") (pintype "passive"))
      (node (ref "C21") (pin "2") (pinfunction "2_2") (pintype "passive"))
      (node (ref "C23") (pin "2") (pinfunction "2_2") (pintype "passive"))
      (node (ref "C24") (pin "2") (pinfunction "2_2") (pintype "passive"))
      (node (ref "C25") (pin "2") (pinfunction "2_2") (pintype "passive"))
      (node (ref "C26") (pin "2") (pinfunction "2_2") (pintype "passive"))
      (node (ref "C27") (pin "2") (pinfunction "2_2") (pintype "passive"))
      (node (ref "C28") (pin "2") (pinfunction "2_2") (pintype "passive"))
      (node (ref "C29") (pin "2") (pinfunction "2_2") (pintype "passive"))
      (node (ref "C30") (pin "2") (pinfunction "2_2") (pintype "passive"))
      (node (ref "C31") (pin "2") (pinfunction "2_2") (pintype "passive"))
      (node (ref "C32") (pin "2") (pinfunction "2_2") (pintype "passive"))
      (node (ref "C35") (pin "1") (pinfunction "1_1") (pintype "passive"))
      (node (ref "C38") (pin "2") (pinfunction "2_2") (pintype "passive"))
      (node (ref "C39") (pin "1") (pinfunction "1_1") (pintype "passive"))
      (node (ref "DP1") (pin "1") (pinfunction "VSS_1") (pintype "passive"))
      (node (ref "DP1") (pin "10") (pinfunction "BS0_10") (pintype "passive"))
      (node (ref "DP1") (pin "11") (pinfunction "BS1_11") (pintype "passive"))
      (node (ref "DP1") (pin "12") (pinfunction "BS2_12") (pintype "passive"))
      (node (ref "DP1") (pin "13") (pinfunction "CS_13") (pintype "passive"))
      (node (ref "DP1") (pin "16") (pinfunction "R/W_16") (pintype "passive"))
      (node (ref "DP1") (pin "17") (pinfunction "E/RD_17") (pintype "passive"))
      (node (ref "DP1") (pin "21") (pinfunction "D3_21") (pintype "passive"))
      (node (ref "DP1") (pin "22") (pinfunction "D4_22") (pintype "passive"))
      (node (ref "DP1") (pin "23") (pinfunction "D5_23") (pintype "passive"))
      (node (ref "DP1") (pin "24") (pinfunction "D6_24") (pintype "passive"))
      (node (ref "DP1") (pin "25") (pinfunction "D7_25") (pintype "passive"))
      (node (ref "DP1") (pin "29") (pinfunction "VLSS_29") (pintype "passive"))
      (node (ref "DP1") (pin "30") (pinfunction "VSS_30") (pintype "passive"))
      (node (ref "DP1") (pin "8") (pinfunction "VSS_8") (pintype "passive"))
      (node (ref "E1") (pin "2") (pinfunction "2_2") (pintype "passive"))
      (node (ref "J10") (pin "3") (pinfunction "3_3") (pintype "passive"))
      (node (ref "J11") (pin "3") (pinfunction "3_3") (pintype "passive"))
      (node (ref "J12") (pin "3") (pinfunction "3_3") (pintype "passive"))
      (node (ref "J13") (pin "1") (pinfunction "1_1") (pintype "passive"))
      (node (ref "J4") (pin "6") (pinfunction "6_6") (pintype "passive"))
      (node (ref "J5") (pin "6") (pinfunction "6_6") (pintype "passive"))
      (node (ref "J6") (pin "1") (pinfunction "1_1") (pintype "passive"))
      (node (ref "J7") (pin "1") (pinfunction "1_1") (pintype "passive"))
      (node (ref "J8") (pin "3") (pinfunction "3_3") (pintype "passive"))
      (node (ref "J9") (pin "8") (pinfunction "8_8") (pintype "passive"))
      (node (ref "JTAG1") (pin "3") (pinfunction "3_3") (pintype "passive"))
      (node (ref "JTAG1") (pin "5") (pinfunction "5_5") (pintype "passive"))
      (node (ref "JTAG1") (pin "7") (pinfunction "7_7") (pintype "passive"))
      (node (ref "JTAG1") (pin "9") (pinfunction "9_9") (pintype "passive"))
      (node (ref "M2") (pin "1") (pinfunction "1_1") (pintype "passive"))
      (node (ref "R13") (pin "1") (pinfunction "1_1") (pintype "passive"))
      (node (ref "R15") (pin "1") (pinfunction "1_1") (pintype "passive"))
      (node (ref "R3") (pin "2") (pinfunction "2_2") (pintype "passive"))
      (node (ref "S3") (pin "2") (pinfunction "2_2") (pintype "passive"))
      (node (ref "S6") (pin "10") (pinfunction "10_10") (pintype "passive"))
      (node (ref "S6") (pin "11") (pinfunction "11_11") (pintype "passive"))
      (node (ref "S6") (pin "12") (pinfunction "12_12") (pintype "passive"))
      (node (ref "S6") (pin "13") (pinfunction "13_13") (pintype "passive"))
      (node (ref "S6") (pin "14") (pinfunction "14_14") (pintype "passive"))
      (node (ref "S6") (pin "15") (pinfunction "15_15") (pintype "passive"))
      (node (ref "S6") (pin "16") (pinfunction "16_16") (pintype "passive"))
      (node (ref "S6") (pin "9") (pinfunction "9_9") (pintype "passive"))
      (node (ref "U1") (pin "41") (pinfunction "VSS_41") (pintype "power_in"))
      (node (ref "U1") (pin "49") (pinfunction "VSS_49") (pintype "power_in"))
      (node (ref "U1") (pin "60") (pinfunction "VSS_60") (pintype "passive"))
      (node (ref "U1") (pin "74") (pinfunction "VSS_74") (pintype "passive"))
      (node (ref "U1") (pin "88") (pinfunction "VSS_88") (pintype "passive"))
      (node (ref "U1") (pin "9") (pinfunction "VSS_9") (pintype "power_in"))
      (node (ref "Y1") (pin "2") (pinfunction "GND_2") (pintype "passive"))
    )
    (net (code "66") (name "MCU_3.3V") (class "Default")
      (node (ref "C14") (pin "1") (pinfunction "1_1") (pintype "passive"))
      (node (ref "C16") (pin "1") (pinfunction "1_1") (pintype "passive"))
      (node (ref "C21") (pin "1") (pinfunction "1_1") (pintype "passive"))
      (node (ref "C23") (pin "1") (pinfunction "1_1") (pintype "passive"))
      (node (ref "C24") (pin "1") (pinfunction "1_1") (pintype "passive"))
      (node (ref "C25") (pin "1") (pinfunction "1_1") (pintype "passive"))
      (node (ref "C26") (pin "1") (pinfunction "1_1") (pintype "passive"))
      (node (ref "C27") (pin "1") (pinfunction "1_1") (pintype "passive"))
      (node (ref "C28") (pin "1") (pinfunction "1_1") (pintype "passive"))
      (node (ref "C29") (pin "1") (pinfunction "1_1") (pintype "passive"))
      (node (ref "C30") (pin "1") (pinfunction "1_1") (pintype "passive"))
      (node (ref "C31") (pin "1") (pinfunction "1_1") (pintype "passive"))
      (node (ref "C32") (pin "1") (pinfunction "1_1") (pintype "passive"))
      (node (ref "DP1") (pin "6") (pinfunction "VBAT_6") (pintype "passive"))
      (node (ref "DP1") (pin "9") (pinfunction "VDD_9") (pintype "passive"))
      (node (ref "J12") (pin "4") (pinfunction "4_4") (pintype "passive"))
      (node (ref "J2") (pin "9") (pinfunction "9_9") (pintype "passive"))
      (node (ref "J9") (pin "7") (pinfunction "7_7") (pintype "passive"))
      (node (ref "JTAG1") (pin "1") (pinfunction "1_1") (pintype "passive"))
      (node (ref "L3") (pin "2") (pinfunction "2_2") (pintype "passive"))
      (node (ref "M1") (pin "1") (pinfunction "1_1") (pintype "passive"))
      (node (ref "R11") (pin "2") (pinfunction "2_2") (pintype "passive"))
      (node (ref "R16") (pin "2") (pinfunction "2_2") (pintype "passive"))
      (node (ref "R4") (pin "2") (pinfunction "2_2") (pintype "passive"))
      (node (ref "R5") (pin "2") (pinfunction "2_2") (pintype "passive"))
      (node (ref "U1") (pin "40") (pinfunction "VDD_40") (pintype "power_in"))
      (node (ref "U1") (pin "48") (pinfunction "VDD_48") (pintype "power_in"))
      (node (ref "U1") (pin "61") (pinfunction "VDD_61") (pintype "passive"))
      (node (ref "U1") (pin "75") (pinfunction "VDD_75") (pintype "passive"))
      (node (ref "U1") (pin "8") (pinfunction "VDD_8") (pintype "power_in"))
      (node (ref "U1") (pin "89") (pinfunction "VDD_89") (pintype "passive"))
      (node (ref "Y1") (pin "4") (pinfunction "VCC_4") (pintype "passive"))
    )
    (net (code "67") (name "Net-(B1-GND)") (class "Default")
      (node (ref "B1") (pin "2") (pinfunction "GND_2") (pintype "passive"))
      (node (ref "Q1") (pin "3") (pinfunction "C_3") (pintype "passive"))
    )
    (net (code "68") (name "Net-(C18-Pad2)") (class "Default")
      (node (ref "C18") (pin "2") (pinfunction "2_2") (pintype "passive"))
      (node (ref "R6") (pin "1") (pinfunction "1_1") (pintype "passive"))
    )
    (net (code "69") (name "Net-(DP1-C1N)") (class "Default")
      (node (ref "C37") (pin "2") (pinfunction "2_2") (pintype "passive"))
      (node (ref "DP1") (pin "5") (pinfunction "C1N_5") (pintype "passive"))
    )
    (net (code "70") (name "Net-(DP1-C1P)") (class "Default")
      (node (ref "C37") (pin "1") (pinfunction "1_1") (pintype "passive"))
      (node (ref "DP1") (pin "4") (pinfunction "C1P_4") (pintype "passive"))
    )
    (net (code "71") (name "Net-(DP1-C2N)") (class "Default")
      (node (ref "C36") (pin "1") (pinfunction "1_1") (pintype "passive"))
      (node (ref "DP1") (pin "3") (pinfunction "C2N_3") (pintype "passive"))
    )
    (net (code "72") (name "Net-(DP1-C2P)") (class "Default")
      (node (ref "C36") (pin "2") (pinfunction "2_2") (pintype "passive"))
      (node (ref "DP1") (pin "2") (pinfunction "C2P_2") (pintype "passive"))
    )
    (net (code "73") (name "Net-(DP1-IREF)") (class "Default")
      (node (ref "DP1") (pin "26") (pinfunction "IREF_26") (pintype "passive"))
      (node (ref "R15") (pin "2") (pinfunction "2_2") (pintype "passive"))
    )
    (net (code "74") (name "Net-(DP1-VCC)") (class "Default")
      (node (ref "C38") (pin "1") (pinfunction "1_1") (pintype "passive"))
      (node (ref "C39") (pin "2") (pinfunction "2_2") (pintype "passive"))
      (node (ref "DP1") (pin "28") (pinfunction "VCC_28") (pintype "passive"))
    )
    (net (code "75") (name "Net-(DP1-VCOM)") (class "Default")
      (node (ref "C35") (pin "2") (pinfunction "2_2") (pintype "passive"))
      (node (ref "DP1") (pin "27") (pinfunction "VCOM_27") (pintype "passive"))
    )
    (net (code "76") (name "Net-(E1-Pad1)") (class "Default")
      (node (ref "E1") (pin "1") (pinfunction "1_1") (pintype "passive"))
      (node (ref "R5") (pin "1") (pinfunction "1_1") (pintype "passive"))
    )
    (net (code "77") (name "Net-(E2-Pad1)") (class "Default")
      (node (ref "E2") (pin "1") (pinfunction "1_1") (pintype "passive"))
      (node (ref "R11") (pin "1") (pinfunction "1_1") (pintype "passive"))
    )
    (net (code "78") (name "Net-(J1-VCC)") (class "Default")
      (node (ref "J1") (pin "1") (pinfunction "VCC_1") (pintype "passive"))
      (node (ref "S1") (pin "2") (pinfunction "2_2") (pintype "passive"))
    )
    (net (code "79") (name "Net-(Q1-B)") (class "Default")
      (node (ref "Q1") (pin "1") (pinfunction "B_1") (pintype "passive"))
      (node (ref "R12") (pin "2") (pinfunction "2_2") (pintype "passive"))
      (node (ref "R14") (pin "2") (pinfunction "2_2") (pintype "passive"))
    )
    (net (code "80") (name "Net-(R13-Pad2)") (class "Default")
      (node (ref "R13") (pin "2") (pinfunction "2_2") (pintype "passive"))
      (node (ref "S4") (pin "1") (pinfunction "1_1") (pintype "passive"))
      (node (ref "S5") (pin "1") (pinfunction "1_1") (pintype "passive"))
      (node (ref "S7") (pin "1") (pinfunction "1_1") (pintype "passive"))
      (node (ref "S8") (pin "1") (pinfunction "1_1") (pintype "passive"))
    )
    (net (code "81") (name "Net-(U1-VOUT33)") (class "Default")
      (node (ref "C19") (pin "2") (pintype "passive"))
      (node (ref "U1") (pin "12") (pinfunction "VOUT33_12") (pintype "bidirectional"))
    )
    (net (code "82") (name "Net-(U1-VREGIN)") (class "Default")
      (node (ref "C20") (pin "2") (pintype "passive"))
      (node (ref "U1") (pin "13") (pinfunction "VREGIN_13") (pintype "passive"))
    )
    (net (code "83") (name "Net-(U2-FB)") (class "Default")
      (node (ref "L1") (pin "1") (pinfunction "1_1") (pintype "passive"))
      (node (ref "U2") (pin "5") (pinfunction "OUT_5") (pintype "power_in"))
      (node (ref "U2") (pin "6") (pinfunction "OUT_6") (pintype "power_in"))
      (node (ref "U2") (pin "7") (pinfunction "FB_7") (pintype "power_in"))
    )
    (net (code "84") (name "Net-(U3-FB)") (class "Default")
      (node (ref "L2") (pin "1") (pinfunction "1_1") (pintype "passive"))
      (node (ref "U3") (pin "5") (pinfunction "OUT_5") (pintype "power_in"))
      (node (ref "U3") (pin "6") (pinfunction "OUT_6") (pintype "power_in"))
      (node (ref "U3") (pin "7") (pinfunction "FB_7") (pintype "power_in"))
    )
    (net (code "85") (name "Net-(U4-ADJ)") (class "Default")
      (node (ref "R1") (pin "1") (pinfunction "1_1") (pintype "passive"))
      (node (ref "R2") (pin "2") (pinfunction "2_2") (pintype "passive"))
      (node (ref "U4") (pin "1") (pinfunction "ADJ_1") (pintype "input"))
    )
    (net (code "86") (name "Net-(U5-FB)") (class "Default")
      (node (ref "L3") (pin "1") (pinfunction "1_1") (pintype "passive"))
      (node (ref "U5") (pin "5") (pinfunction "OUT_5") (pintype "power_in"))
      (node (ref "U5") (pin "6") (pinfunction "OUT_6") (pintype "power_in"))
      (node (ref "U5") (pin "7") (pinfunction "FB_7") (pintype "power_in"))
    )
    (net (code "87") (name "VDDA") (class "Default")
      (node (ref "C33") (pin "1") (pinfunction "1_1") (pintype "passive"))
      (node (ref "C34") (pin "1") (pinfunction "1_1") (pintype "passive"))
      (node (ref "M1") (pin "2") (pinfunction "2_2") (pintype "passive"))
      (node (ref "R9") (pin "1") (pinfunction "1_1") (pintype "passive"))
      (node (ref "U1") (pin "22") (pinfunction "VDDA_22") (pintype "power_in"))
    )
    (net (code "88") (name "VRH") (class "Default")
      (node (ref "R9") (pin "2") (pinfunction "2_2") (pintype "passive"))
      (node (ref "U1") (pin "23") (pinfunction "VREFH_23") (pintype "power_in"))
    )
    (net (code "89") (name "VRL") (class "Default")
      (node (ref "R10") (pin "2") (pinfunction "2_2") (pintype "passive"))
      (node (ref "U1") (pin "24") (pinfunction "VREFL_24") (pintype "power_in"))
    )
    (net (code "90") (name "VSSA") (class "Default")
      (node (ref "C33") (pin "2") (pinfunction "2_2") (pintype "passive"))
      (node (ref "C34") (pin "2") (pinfunction "2_2") (pintype "passive"))
      (node (ref "M2") (pin "2") (pinfunction "2_2") (pintype "passive"))
      (node (ref "R10") (pin "1") (pinfunction "1_1") (pintype "passive"))
      (node (ref "U1") (pin "25") (pinfunction "VSSA_25") (pintype "power_in"))
    )
    (net (code "91") (name "unconnected-(DP1-D2-Pad20)") (class "Default")
      (node (ref "DP1") (pin "20") (pinfunction "D2_20") (pintype "passive"))
    )
    (net (code "92") (name "unconnected-(DP1-NC-Pad7)") (class "Default")
      (node (ref "DP1") (pin "7") (pinfunction "NC_7") (pintype "passive"))
    )
    (net (code "93") (name "unconnected-(F1-MH1-Pad5)") (class "Default")
      (node (ref "F1") (pin "5") (pinfunction "MH1_5") (pintype "passive"))
    )
    (net (code "94") (name "unconnected-(F1-MH2-Pad6)") (class "Default")
      (node (ref "F1") (pin "6") (pinfunction "MH2_6") (pintype "passive"))
    )
    (net (code "95") (name "unconnected-(J6-Pad5)") (class "Default")
      (node (ref "J6") (pin "5") (pinfunction "5_5") (pintype "passive"))
    )
    (net (code "96") (name "unconnected-(J6-Pad6)") (class "Default")
      (node (ref "J6") (pin "6") (pinfunction "6_6") (pintype "passive"))
    )
    (net (code "97") (name "unconnected-(J7-Pad5)") (class "Default")
      (node (ref "J7") (pin "5") (pinfunction "5_5") (pintype "passive"))
    )
    (net (code "98") (name "unconnected-(J7-Pad6)") (class "Default")
      (node (ref "J7") (pin "6") (pinfunction "6_6") (pintype "passive"))
    )
    (net (code "99") (name "unconnected-(J10-Pad1)") (class "Default")
      (node (ref "J10") (pin "1") (pinfunction "1_1") (pintype "passive"))
    )
    (net (code "100") (name "unconnected-(J11-Pad1)") (class "Default")
      (node (ref "J11") (pin "1") (pinfunction "1_1") (pintype "passive"))
    )
    (net (code "101") (name "unconnected-(R16-Pad1)") (class "Default")
      (node (ref "R16") (pin "1") (pinfunction "1_1") (pintype "passive"))
    )
    (net (code "102") (name "unconnected-(S1-Pad1)") (class "Default")
      (node (ref "S1") (pin "1") (pinfunction "1_1") (pintype "passive"))
    )
    (net (code "103") (name "unconnected-(S2-Pad1)") (class "Default")
      (node (ref "S2") (pin "1") (pinfunction "1_1") (pintype "passive"))
    )
    (net (code "104") (name "unconnected-(U1-ADC0_DM1-Pad15)") (class "Default")
      (node (ref "U1") (pin "15") (pinfunction "ADC0_DM1_15") (pintype "bidirectional"))
    )
    (net (code "105") (name "unconnected-(U1-ADC0_DM3-Pad21)") (class "Default")
      (node (ref "U1") (pin "21") (pinfunction "ADC0_DM3_21") (pintype "bidirectional"))
    )
    (net (code "106") (name "unconnected-(U1-ADC0_DP1-Pad14)") (class "Default")
      (node (ref "U1") (pin "14") (pinfunction "ADC0_DP1_14") (pintype "bidirectional"))
    )
    (net (code "107") (name "unconnected-(U1-ADC0_DP3-Pad20)") (class "Default")
      (node (ref "U1") (pin "20") (pinfunction "ADC0_DP3_20") (pintype "bidirectional"))
    )
    (net (code "108") (name "unconnected-(U1-ADC1_DM1-Pad17)") (class "Default")
      (node (ref "U1") (pin "17") (pinfunction "ADC1_DM1_17") (pintype "bidirectional"))
    )
    (net (code "109") (name "unconnected-(U1-ADC1_DM3-Pad19)") (class "Default")
      (node (ref "U1") (pin "19") (pinfunction "ADC1_DM3_19") (pintype "bidirectional"))
    )
    (net (code "110") (name "unconnected-(U1-ADC1_DP1-Pad16)") (class "Default")
      (node (ref "U1") (pin "16") (pinfunction "ADC1_DP1_16") (pintype "bidirectional"))
    )
    (net (code "111") (name "unconnected-(U1-ADC1_DP3-Pad18)") (class "Default")
      (node (ref "U1") (pin "18") (pinfunction "ADC1_DP3_18") (pintype "bidirectional"))
    )
    (net (code "112") (name "unconnected-(U1-DAC0_OUT-Pad27)") (class "Default")
      (node (ref "U1") (pin "27") (pinfunction "DAC0_OUT_27") (pintype "bidirectional"))
    )
    (net (code "113") (name "unconnected-(U1-EXTAL32-Pad29)") (class "Default")
      (node (ref "U1") (pin "29") (pinfunction "EXTAL32_29") (pintype "passive"))
    )
    (net (code "114") (name "unconnected-(U1-PTA4-Pad38)") (class "Default")
      (node (ref "U1") (pin "38") (pinfunction "PTA4_38") (pintype "bidirectional"))
    )
    (net (code "115") (name "unconnected-(U1-PTA12-Pad42)") (class "Default")
      (node (ref "U1") (pin "42") (pinfunction "PTA12_42") (pintype "bidirectional"))
    )
    (net (code "116") (name "unconnected-(U1-PTA13-Pad43)") (class "Default")
      (node (ref "U1") (pin "43") (pinfunction "PTA13_43") (pintype "bidirectional"))
    )
    (net (code "117") (name "unconnected-(U1-PTA14-Pad44)") (class "Default")
      (node (ref "U1") (pin "44") (pinfunction "PTA14_44") (pintype "bidirectional"))
    )
    (net (code "118") (name "unconnected-(U1-PTA15-Pad45)") (class "Default")
      (node (ref "U1") (pin "45") (pinfunction "PTA15_45") (pintype "bidirectional"))
    )
    (net (code "119") (name "unconnected-(U1-PTA16-Pad46)") (class "Default")
      (node (ref "U1") (pin "46") (pinfunction "PTA16_46") (pintype "bidirectional"))
    )
    (net (code "120") (name "unconnected-(U1-PTC14-Pad86)") (class "Default")
      (node (ref "U1") (pin "86") (pinfunction "PTC14_86") (pintype "bidirectional"))
    )
    (net (code "121") (name "unconnected-(U1-PTC15-Pad87)") (class "Default")
      (node (ref "U1") (pin "87") (pinfunction "PTC15_87") (pintype "bidirectional"))
    )
    (net (code "122") (name "unconnected-(U1-PTE26-Pad33)") (class "Default")
      (node (ref "U1") (pin "33") (pinfunction "PTE26_33") (pintype "bidirectional"))
    )
    (net (code "123") (name "unconnected-(U1-USB0_DM-Pad11)") (class "Default")
      (node (ref "U1") (pin "11") (pinfunction "USB0_DM_11") (pintype "bidirectional"))
    )
    (net (code "124") (name "unconnected-(U1-USB0_DP-Pad10)") (class "Default")
      (node (ref "U1") (pin "10") (pinfunction "USB0_DP_10") (pintype "bidirectional"))
    )
    (net (code "125") (name "unconnected-(U1-VBAT-Pad30)") (class "Default")
      (node (ref "U1") (pin "30") (pinfunction "VBAT_30") (pintype "passive"))
    )
    (net (code "126") (name "unconnected-(U1-VREF_OUT-Pad26)") (class "Default")
      (node (ref "U1") (pin "26") (pinfunction "VREF_OUT_26") (pintype "bidirectional"))
    )
    (net (code "127") (name "unconnected-(U1-XTAL-Pad51)") (class "Default")
      (node (ref "U1") (pin "51") (pinfunction "XTAL_51") (pintype "passive"))
    )
    (net (code "128") (name "unconnected-(U1-XTAL32-Pad28)") (class "Default")
      (node (ref "U1") (pin "28") (pinfunction "XTAL32_28") (pintype "passive"))
    )
    (net (code "129") (name "unconnected-(U2-~{RESET}-Pad8)") (class "Default")
      (node (ref "U2") (pin "8") (pinfunction "~{RESET}_8") (pintype "power_in"))
    )
    (net (code "130") (name "unconnected-(U3-~{RESET}-Pad8)") (class "Default")
      (node (ref "U3") (pin "8") (pinfunction "~{RESET}_8") (pintype "power_in"))
    )
    (net (code "131") (name "unconnected-(U5-~{RESET}-Pad8)") (class "Default")
      (node (ref "U5") (pin "8") (pinfunction "~{RESET}_8") (pintype "power_in"))
    )
    (net (code "132") (name "unconnected-(Y1-NC-Pad1)") (class "Default")
      (node (ref "Y1") (pin "1") (pinfunction "NC_1") (pintype "passive"))
    )
  )
)
